# SCH_FT232H.net
KiCad netlist of a schematic drawn in Altium Designer
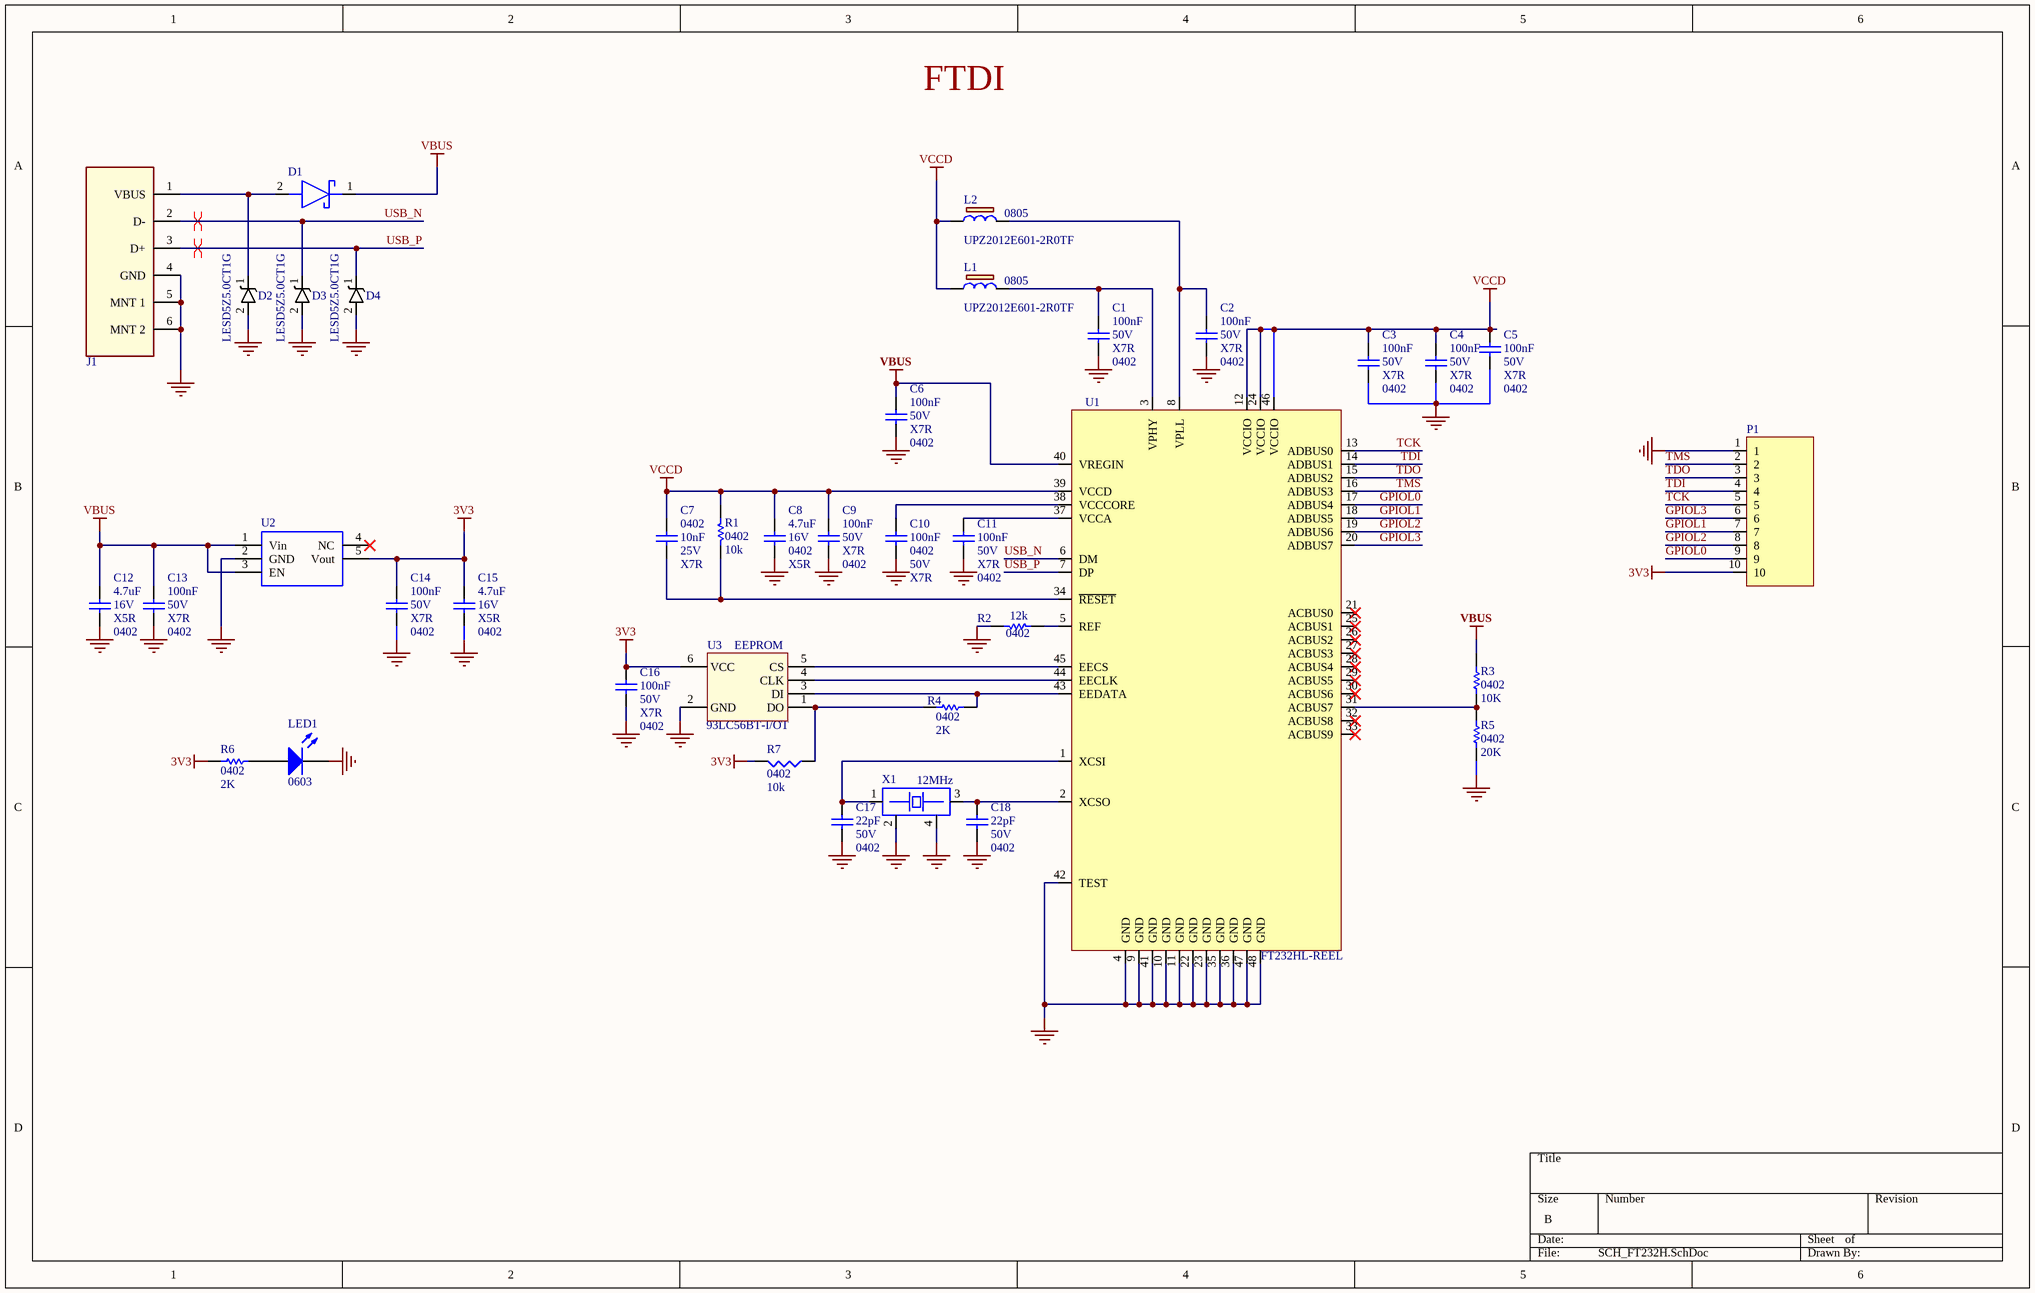
[diagram p0: SCH_FT232H.SchDoc]

(export (version "E")
  (design (tool "Eeschema 10.0.6"))
  (components
    (comp (ref "C1")
      (value "100nF")
      (footprint "CAPC0402")
      (description "CAP CER 100nF 50V X7R 0402")
      (fields
        (field (name "CASE/PACKAGE") "0402")
        (field (name "VOLTAGE") "50V")
        (field (name "DIELECTRIC") "X7R")
      )
      (libsource (lib "Pd's Sch Lib") (part "Capacitor"))
    )
    (comp (ref "C2")
      (value "100nF")
      (footprint "CAPC0402")
      (description "CAP CER 100nF 50V X7R 0402")
      (fields
        (field (name "CASE/PACKAGE") "0402")
        (field (name "VOLTAGE") "50V")
        (field (name "DIELECTRIC") "X7R")
      )
      (libsource (lib "Pd's Sch Lib") (part "Capacitor"))
    )
    (comp (ref "C3")
      (value "100nF")
      (footprint "CAPC0402")
      (description "CAP CER 100nF 50V X7R 0402")
      (fields
        (field (name "CASE/PACKAGE") "0402")
        (field (name "VOLTAGE") "50V")
        (field (name "DIELECTRIC") "X7R")
      )
      (libsource (lib "Pd's Sch Lib") (part "Capacitor"))
    )
    (comp (ref "C4")
      (value "100nF")
      (footprint "CAPC0402")
      (description "CAP CER 100nF 50V X7R 0402")
      (fields
        (field (name "CASE/PACKAGE") "0402")
        (field (name "VOLTAGE") "50V")
        (field (name "DIELECTRIC") "X7R")
      )
      (libsource (lib "Pd's Sch Lib") (part "Capacitor"))
    )
    (comp (ref "C5")
      (value "100nF")
      (footprint "CAPC0402")
      (description "CAP CER 100nF 50V X7R 0402")
      (fields
        (field (name "CASE/PACKAGE") "0402")
        (field (name "VOLTAGE") "50V")
        (field (name "DIELECTRIC") "X7R")
      )
      (libsource (lib "Pd's Sch Lib") (part "Capacitor"))
    )
    (comp (ref "C6")
      (value "100nF")
      (footprint "CAPC0402")
      (description "CAP CER 100nF 50V X7R 0402")
      (fields
        (field (name "CASE/PACKAGE") "0402")
        (field (name "VOLTAGE") "50V")
        (field (name "DIELECTRIC") "X7R")
      )
      (libsource (lib "Pd's Sch Lib") (part "Capacitor"))
    )
    (comp (ref "C7")
      (value "10nF")
      (footprint "CAPC0402")
      (description "CAP CER 10nF 25V X7R 0402")
      (fields
        (field (name "CASE/PACKAGE") "0402")
        (field (name "VOLTAGE") "25V")
        (field (name "DIELECTRIC") "X7R")
      )
      (libsource (lib "Pd's Sch Lib") (part "Capacitor"))
    )
    (comp (ref "C8")
      (value "4.7uF")
      (footprint "CAPC0402")
      (description "CAP CER 4.7uF 16V X5R 0402")
      (fields
        (field (name "CASE/PACKAGE") "0402")
        (field (name "VOLTAGE") "16V")
        (field (name "DIELECTRIC") "X5R")
      )
      (libsource (lib "Pd's Sch Lib") (part "Capacitor"))
    )
    (comp (ref "C9")
      (value "100nF")
      (footprint "CAPC0402")
      (description "CAP CER 100nF 50V X7R 0402")
      (fields
        (field (name "CASE/PACKAGE") "0402")
        (field (name "VOLTAGE") "50V")
        (field (name "DIELECTRIC") "X7R")
      )
      (libsource (lib "Pd's Sch Lib") (part "Capacitor"))
    )
    (comp (ref "C10")
      (value "100nF")
      (footprint "CAPC0402")
      (description "CAP CER 100nF 50V X7R 0402")
      (fields
        (field (name "CASE/PACKAGE") "0402")
        (field (name "VOLTAGE") "50V")
        (field (name "DIELECTRIC") "X7R")
      )
      (libsource (lib "Pd's Sch Lib") (part "Capacitor"))
    )
    (comp (ref "C11")
      (value "100nF")
      (footprint "CAPC0402")
      (description "CAP CER 100nF 50V X7R 0402")
      (fields
        (field (name "CASE/PACKAGE") "0402")
        (field (name "VOLTAGE") "50V")
        (field (name "DIELECTRIC") "X7R")
      )
      (libsource (lib "Pd's Sch Lib") (part "Capacitor"))
    )
    (comp (ref "C12")
      (value "4.7uF")
      (footprint "CAPC0402")
      (description "CAP CER 4.7uF 16V X5R 0402")
      (fields
        (field (name "CASE/PACKAGE") "0402")
        (field (name "VOLTAGE") "16V")
        (field (name "DIELECTRIC") "X5R")
      )
      (libsource (lib "Pd's Sch Lib") (part "Capacitor"))
    )
    (comp (ref "C13")
      (value "100nF")
      (footprint "CAPC0402")
      (description "CAP CER 100nF 50V X7R 0402")
      (fields
        (field (name "CASE/PACKAGE") "0402")
        (field (name "VOLTAGE") "50V")
        (field (name "DIELECTRIC") "X7R")
      )
      (libsource (lib "Pd's Sch Lib") (part "Capacitor"))
    )
    (comp (ref "C14")
      (value "100nF")
      (footprint "CAPC0402")
      (description "CAP CER 100nF 50V X7R 0402")
      (fields
        (field (name "CASE/PACKAGE") "0402")
        (field (name "VOLTAGE") "50V")
        (field (name "DIELECTRIC") "X7R")
      )
      (libsource (lib "Pd's Sch Lib") (part "Capacitor"))
    )
    (comp (ref "C15")
      (value "4.7uF")
      (footprint "CAPC0402")
      (description "CAP CER 4.7uF 16V X5R 0402")
      (fields
        (field (name "CASE/PACKAGE") "0402")
        (field (name "VOLTAGE") "16V")
        (field (name "DIELECTRIC") "X5R")
      )
      (libsource (lib "Pd's Sch Lib") (part "Capacitor"))
    )
    (comp (ref "C16")
      (value "100nF")
      (footprint "CAPC0402")
      (description "CAP CER 100nF 50V X7R 0402")
      (fields
        (field (name "CASE/PACKAGE") "0402")
        (field (name "VOLTAGE") "50V")
        (field (name "DIELECTRIC") "X7R")
      )
      (libsource (lib "Pd's Sch Lib") (part "Capacitor"))
    )
    (comp (ref "C17")
      (value "22pF")
      (footprint "CAPC0402")
      (description "CAP CER 22pF 50V 0402")
      (fields (field (name "CASE/PACKAGE") "0402") (field (name "VOLTAGE") "50V"))
      (libsource (lib "Pd's Sch Lib") (part "Capacitor"))
    )
    (comp (ref "C18")
      (value "22pF")
      (footprint "CAPC0402")
      (description "CAP CER 22pF 50V 0402")
      (fields (field (name "CASE/PACKAGE") "0402") (field (name "VOLTAGE") "50V"))
      (libsource (lib "Pd's Sch Lib") (part "Capacitor"))
    )
    (comp (ref "D1")
      (value "~")
      (footprint "BAT760-7")
      (description "DIODE SCHOTTKY 40V 1A SOD323")
      (fields (field (name "MANUFACTURER PART NUMBER") "B5819WS"))
      (libsource (lib "CUSTOM SCH") (part "B5819WS"))
    )
    (comp (ref "D2")
      (value "~")
      (footprint "SOD523")
      (description "12.3V Clamp 8.7A (8/20µs) Ipp Tvs Diode Surface Mount SOD-523")
      (fields (field (name "MANUFACTURER PART NUMBER") "LESD5Z5.0CT1G"))
      (libsource (lib "CUSTOM TNY290PG") (part "ESD9X5.0ST5G"))
    )
    (comp (ref "D3")
      (value "~")
      (footprint "SOD523")
      (description "12.3V Clamp 8.7A (8/20µs) Ipp Tvs Diode Surface Mount SOD-523")
      (fields (field (name "MANUFACTURER PART NUMBER") "LESD5Z5.0CT1G"))
      (libsource (lib "CUSTOM TNY290PG") (part "ESD9X5.0ST5G"))
    )
    (comp (ref "D4")
      (value "~")
      (footprint "SOD523")
      (description "12.3V Clamp 8.7A (8/20µs) Ipp Tvs Diode Surface Mount SOD-523")
      (fields (field (name "MANUFACTURER PART NUMBER") "LESD5Z5.0CT1G"))
      (libsource (lib "CUSTOM TNY290PG") (part "ESD9X5.0ST5G"))
    )
    (comp (ref "J1")
      (value "~")
      (footprint "Molex_48037-0001_0")
      (description "USB A-type Plug Male PCB R/A")
      (fields (field (name "MANUFACTURER PART NUMBER") "USB Type A male"))
      (libsource (lib "CUSTOM TNY290PG") (part "USB MALE"))
    )
    (comp (ref "L1")
      (value "~")
      (footprint "ferrite bead 600R 0.5A")
      (description "Ferrite Beads 600 OHM 25% 2A")
      (fields
        (field (name "MANUFACTURER PART NUMBER") "UPZ2012E601-2R0TF")
        (field (name "CASE/PACKAGE") "0805")
      )
      (libsource (lib "CUSTOM SCH") (part "Ferrite Bead"))
    )
    (comp (ref "L2")
      (value "~")
      (footprint "ferrite bead 600R 0.5A")
      (description "Ferrite Beads 600 OHM 25% 2A")
      (fields
        (field (name "MANUFACTURER PART NUMBER") "UPZ2012E601-2R0TF")
        (field (name "CASE/PACKAGE") "0805")
      )
      (libsource (lib "CUSTOM SCH") (part "Ferrite Bead"))
    )
    (comp (ref "LED1")
      (value "~")
      (footprint "led_0603")
      (description "RED LED 0603")
      (fields (field (name "CASE/PACKAGE") "0603"))
      (libsource (lib "VEGG_Schlib") (part "LED"))
    )
    (comp (ref "P1")
      (value "~")
      (footprint "10 pin smd")
      (description "Header, 10-Pin")
      (fields (field (name "MANUFACTURER PART NUMBER") "17-Jul-2002"))
      (libsource (lib "Pd's Sch Lib") (part "Header 10"))
    )
    (comp (ref "R1")
      (value "10k")
      (footprint "RESC0402")
      (description "Thick Film Resistor -  10Kohm, 1%, 0402")
      (fields (field (name "CASE/PACKAGE") "0402"))
      (libsource (lib "Miscellaneous Devices") (part "Res1"))
    )
    (comp (ref "R2")
      (value "12k")
      (footprint "RESC0402")
      (description "Thick Film Resistor -  12Kohm, 1%, 0402")
      (fields (field (name "CASE/PACKAGE") "0402"))
      (libsource (lib "Miscellaneous Devices") (part "Res1"))
    )
    (comp (ref "R3")
      (value "10K")
      (footprint "RESC0402")
      (description "Thick Film Resistor -  10Kohm, 1%, 0402")
      (fields (field (name "CASE/PACKAGE") "0402"))
      (libsource (lib "Miscellaneous Devices") (part "Res1"))
    )
    (comp (ref "R4")
      (value "2K")
      (footprint "RESC0402")
      (description "Thick Film Resistor -  2Kohm, 1%, 0402")
      (fields (field (name "CASE/PACKAGE") "0402"))
      (libsource (lib "Miscellaneous Devices") (part "Res1"))
    )
    (comp (ref "R5")
      (value "20K")
      (footprint "RESC0402")
      (description "Thick Film Resistor -  20Kohm, 1%, 0402")
      (fields (field (name "CASE/PACKAGE") "0402"))
      (libsource (lib "Miscellaneous Devices") (part "Res1"))
    )
    (comp (ref "R6")
      (value "2K")
      (footprint "RESC0402")
      (description "Thick Film Resistor -  2Kohm, 1%, 0402")
      (fields (field (name "CASE/PACKAGE") "0402"))
      (libsource (lib "Miscellaneous Devices") (part "Res1"))
    )
    (comp (ref "R7")
      (value "10k")
      (footprint "RESC0402")
      (description "Thick Film Resistor -  10Kohm, 1%, 0402")
      (fields (field (name "CASE/PACKAGE") "0402"))
      (libsource (lib "CUSTOM TNY290PG") (part "Res"))
    )
    (comp (ref "U1")
      (value "~")
      (footprint "LQFP-48_7x7x05P__  FT232HL-REEL")
      (description "USB Interface IC USB HS to UART/FIFO SPI/JTAG/I2C LQFP-48")
      (fields (field (name "MANUFACTURER PART NUMBER") "FT232HL-REEL"))
      (libsource (lib "Pd's Sch Lib") (part "FT232HL"))
    )
    (comp (ref "U2")
      (value "~")
      (footprint "SOT25")
      (description "LDO Voltage Regulators 600mA CMOS LDO 50mA 3.3V 250mV")
      (fields (field (name "MANUFACTURER PART NUMBER") "AP2112K-3.3TRG1"))
      (libsource (lib "VEGG_Schlib") (part "LDO_5V_3V"))
    )
    (comp (ref "U3")
      (value "~")
      (footprint "SOT-23-6")
      (description "MICROCHIP - 93LC56BT-I/OT. - 2K, 128 X 16, SERIAL EE, IND ROHS COMPLIANT: YES")
      (fields
        (field (name "MANUFACTURER") "Microchip")
        (field (name "MEMORY TYPE") "EEPROM")
        (field (name "MANUFACTURER PART NUMBER") "93LC56BT-I/OT")
      )
      (libsource (lib "CUSTOM TNY290PG") (part "93LC56BT-I/OT"))
    )
    (comp (ref "X1")
      (value "~")
      (footprint "Crystal_3225")
      (description "CRYSTAL 12.0000MHZ 10PF SMD")
      (fields
        (field (name "MANUFACTURER PART NUMBER") "ECS-120-10-33B-CKM-TR")
        (field (name "FREQUENCY") "12MHz")
      )
      (libsource (lib "Pd's Sch Lib") (part "CRYSTAL_1_1"))
    )
  )
  (nets
    (net (code "1") (name "/GPIOL0") (class "Default")
      (node (ref "P1") (pin "9") (pinfunction "9_9") (pintype "passive"))
      (node (ref "U1") (pin "17") (pinfunction "ADBUS4_17") (pintype "passive"))
    )
    (net (code "2") (name "/GPIOL1") (class "Default")
      (node (ref "P1") (pin "7") (pinfunction "7_7") (pintype "passive"))
      (node (ref "U1") (pin "18") (pinfunction "ADBUS5_18") (pintype "passive"))
    )
    (net (code "3") (name "/GPIOL2") (class "Default")
      (node (ref "P1") (pin "8") (pinfunction "8_8") (pintype "passive"))
      (node (ref "U1") (pin "19") (pinfunction "ADBUS6_19") (pintype "passive"))
    )
    (net (code "4") (name "/GPIOL3") (class "Default")
      (node (ref "P1") (pin "6") (pinfunction "6_6") (pintype "passive"))
      (node (ref "U1") (pin "20") (pinfunction "ADBUS7_20") (pintype "passive"))
    )
    (net (code "5") (name "/TCK") (class "Default")
      (node (ref "P1") (pin "5") (pinfunction "5_5") (pintype "passive"))
      (node (ref "U1") (pin "13") (pinfunction "ADBUS0_13") (pintype "passive"))
    )
    (net (code "6") (name "/TDI") (class "Default")
      (node (ref "P1") (pin "4") (pinfunction "4_4") (pintype "passive"))
      (node (ref "U1") (pin "14") (pinfunction "ADBUS1_14") (pintype "passive"))
    )
    (net (code "7") (name "/TDO") (class "Default")
      (node (ref "P1") (pin "3") (pinfunction "3_3") (pintype "passive"))
      (node (ref "U1") (pin "15") (pinfunction "ADBUS2_15") (pintype "passive"))
    )
    (net (code "8") (name "/TMS") (class "Default")
      (node (ref "P1") (pin "2") (pinfunction "2_2") (pintype "passive"))
      (node (ref "U1") (pin "16") (pinfunction "ADBUS3_16") (pintype "passive"))
    )
    (net (code "9") (name "/USB_N") (class "Default")
      (node (ref "D3") (pin "1") (pinfunction "K_1") (pintype "passive"))
      (node (ref "J1") (pin "2") (pinfunction "D-_2") (pintype "passive"))
      (node (ref "U1") (pin "6") (pinfunction "DM_6") (pintype "passive"))
    )
    (net (code "10") (name "/USB_P") (class "Default")
      (node (ref "D4") (pin "1") (pinfunction "K_1") (pintype "passive"))
      (node (ref "J1") (pin "3") (pinfunction "D+_3") (pintype "passive"))
      (node (ref "U1") (pin "7") (pinfunction "DP_7") (pintype "passive"))
    )
    (net (code "11") (name "3V3") (class "Default")
      (node (ref "C14") (pin "2") (pinfunction "2_2") (pintype "passive"))
      (node (ref "C15") (pin "2") (pinfunction "2_2") (pintype "passive"))
      (node (ref "C16") (pin "2") (pinfunction "2_2") (pintype "passive"))
      (node (ref "P1") (pin "10") (pinfunction "10_10") (pintype "passive"))
      (node (ref "R6") (pin "1") (pinfunction "1_1") (pintype "passive"))
      (node (ref "R7") (pin "2") (pinfunction "2_2") (pintype "passive"))
      (node (ref "U2") (pin "5") (pinfunction "Vout_5") (pintype "power_in"))
      (node (ref "U3") (pin "6") (pinfunction "VCC_6") (pintype "passive"))
    )
    (net (code "12") (name "GND") (class "Default")
      (node (ref "C1") (pin "1") (pinfunction "1_1") (pintype "passive"))
      (node (ref "C10") (pin "1") (pinfunction "1_1") (pintype "passive"))
      (node (ref "C11") (pin "1") (pinfunction "1_1") (pintype "passive"))
      (node (ref "C12") (pin "1") (pinfunction "1_1") (pintype "passive"))
      (node (ref "C13") (pin "1") (pinfunction "1_1") (pintype "passive"))
      (node (ref "C14") (pin "1") (pinfunction "1_1") (pintype "passive"))
      (node (ref "C15") (pin "1") (pinfunction "1_1") (pintype "passive"))
      (node (ref "C16") (pin "1") (pinfunction "1_1") (pintype "passive"))
      (node (ref "C17") (pin "1") (pinfunction "1_1") (pintype "passive"))
      (node (ref "C18") (pin "1") (pinfunction "1_1") (pintype "passive"))
      (node (ref "C2") (pin "1") (pinfunction "1_1") (pintype "passive"))
      (node (ref "C3") (pin "2") (pinfunction "2_2") (pintype "passive"))
      (node (ref "C4") (pin "2") (pinfunction "2_2") (pintype "passive"))
      (node (ref "C5") (pin "2") (pinfunction "2_2") (pintype "passive"))
      (node (ref "C6") (pin "1") (pinfunction "1_1") (pintype "passive"))
      (node (ref "C8") (pin "1") (pinfunction "1_1") (pintype "passive"))
      (node (ref "C9") (pin "1") (pinfunction "1_1") (pintype "passive"))
      (node (ref "D2") (pin "2") (pinfunction "A_2") (pintype "passive"))
      (node (ref "D3") (pin "2") (pinfunction "A_2") (pintype "passive"))
      (node (ref "D4") (pin "2") (pinfunction "A_2") (pintype "passive"))
      (node (ref "J1") (pin "4") (pinfunction "GND_4") (pintype "passive"))
      (node (ref "J1") (pin "5") (pinfunction "MNT_1_5") (pintype "passive"))
      (node (ref "J1") (pin "6") (pinfunction "MNT_2_6") (pintype "passive"))
      (node (ref "LED1") (pin "K") (pinfunction "K_K") (pintype "passive"))
      (node (ref "P1") (pin "1") (pinfunction "1_1") (pintype "passive"))
      (node (ref "R2") (pin "1") (pinfunction "1_1") (pintype "passive"))
      (node (ref "R5") (pin "2") (pinfunction "2_2") (pintype "passive"))
      (node (ref "U1") (pin "10") (pinfunction "GND_10") (pintype "passive"))
      (node (ref "U1") (pin "11") (pinfunction "GND_11") (pintype "passive"))
      (node (ref "U1") (pin "22") (pinfunction "GND_22") (pintype "passive"))
      (node (ref "U1") (pin "23") (pinfunction "GND_23") (pintype "passive"))
      (node (ref "U1") (pin "35") (pinfunction "GND_35") (pintype "passive"))
      (node (ref "U1") (pin "36") (pinfunction "GND_36") (pintype "passive"))
      (node (ref "U1") (pin "4") (pinfunction "GND_4") (pintype "passive"))
      (node (ref "U1") (pin "41") (pinfunction "GND_41") (pintype "passive"))
      (node (ref "U1") (pin "42") (pinfunction "TEST_42") (pintype "passive"))
      (node (ref "U1") (pin "47") (pinfunction "GND_47") (pintype "passive"))
      (node (ref "U1") (pin "48") (pinfunction "GND_48") (pintype "passive"))
      (node (ref "U1") (pin "9") (pinfunction "GND_9") (pintype "passive"))
      (node (ref "U2") (pin "2") (pinfunction "GND_2") (pintype "power_in"))
      (node (ref "U3") (pin "2") (pinfunction "GND_2") (pintype "passive"))
      (node (ref "X1") (pin "2") (pinfunction "2_2") (pintype "passive"))
      (node (ref "X1") (pin "4") (pinfunction "4_4") (pintype "passive"))
    )
    (net (code "13") (name "Net-(D1-A)") (class "Default")
      (node (ref "D1") (pin "2") (pinfunction "A_2") (pintype "passive"))
      (node (ref "D2") (pin "1") (pinfunction "K_1") (pintype "passive"))
      (node (ref "J1") (pin "1") (pinfunction "VBUS_1") (pintype "passive"))
    )
    (net (code "14") (name "Net-(LED1-PadA)") (class "Default")
      (node (ref "LED1") (pin "A") (pinfunction "A_A") (pintype "passive"))
      (node (ref "R6") (pin "2") (pinfunction "2_2") (pintype "passive"))
    )
    (net (code "15") (name "Net-(U1-ACBUS7)") (class "Default")
      (node (ref "R3") (pin "2") (pinfunction "2_2") (pintype "passive"))
      (node (ref "R5") (pin "1") (pinfunction "1_1") (pintype "passive"))
      (node (ref "U1") (pin "31") (pinfunction "ACBUS7_31") (pintype "passive"))
    )
    (net (code "16") (name "Net-(U1-EECLK)") (class "Default")
      (node (ref "U1") (pin "44") (pinfunction "EECLK_44") (pintype "passive"))
      (node (ref "U3") (pin "4") (pinfunction "CLK_4") (pintype "passive"))
    )
    (net (code "17") (name "Net-(U1-EECS)") (class "Default")
      (node (ref "U1") (pin "45") (pinfunction "EECS_45") (pintype "passive"))
      (node (ref "U3") (pin "5") (pinfunction "CS_5") (pintype "passive"))
    )
    (net (code "18") (name "Net-(U1-EEDATA)") (class "Default")
      (node (ref "R4") (pin "2") (pinfunction "2_2") (pintype "passive"))
      (node (ref "U1") (pin "43") (pinfunction "EEDATA_43") (pintype "passive"))
      (node (ref "U3") (pin "3") (pinfunction "DI_3") (pintype "passive"))
    )
    (net (code "19") (name "Net-(U1-REF)") (class "Default")
      (node (ref "R2") (pin "2") (pinfunction "2_2") (pintype "passive"))
      (node (ref "U1") (pin "5") (pinfunction "REF_5") (pintype "passive"))
    )
    (net (code "20") (name "Net-(U1-VCCA)") (class "Default")
      (node (ref "C11") (pin "2") (pinfunction "2_2") (pintype "passive"))
      (node (ref "U1") (pin "37") (pinfunction "VCCA_37") (pintype "passive"))
    )
    (net (code "21") (name "Net-(U1-VCCCORE)") (class "Default")
      (node (ref "C10") (pin "2") (pinfunction "2_2") (pintype "passive"))
      (node (ref "U1") (pin "38") (pinfunction "VCCCORE_38") (pintype "passive"))
    )
    (net (code "22") (name "Net-(U1-VPHY)") (class "Default")
      (node (ref "C1") (pin "2") (pinfunction "2_2") (pintype "passive"))
      (node (ref "L1") (pin "2") (pintype "passive"))
      (node (ref "U1") (pin "3") (pinfunction "VPHY_3") (pintype "passive"))
    )
    (net (code "23") (name "Net-(U1-VPLL)") (class "Default")
      (node (ref "C2") (pin "2") (pinfunction "2_2") (pintype "passive"))
      (node (ref "L2") (pin "2") (pintype "passive"))
      (node (ref "U1") (pin "8") (pinfunction "VPLL_8") (pintype "passive"))
    )
    (net (code "24") (name "Net-(U1-XCSI)") (class "Default")
      (node (ref "C17") (pin "2") (pinfunction "2_2") (pintype "passive"))
      (node (ref "U1") (pin "1") (pinfunction "XCSI_1") (pintype "passive"))
      (node (ref "X1") (pin "1") (pinfunction "1_1") (pintype "passive"))
    )
    (net (code "25") (name "Net-(U1-XCSO)") (class "Default")
      (node (ref "C18") (pin "2") (pinfunction "2_2") (pintype "passive"))
      (node (ref "U1") (pin "2") (pinfunction "XCSO_2") (pintype "passive"))
      (node (ref "X1") (pin "3") (pinfunction "3_3") (pintype "passive"))
    )
    (net (code "26") (name "Net-(U1-~{RESET})") (class "Default")
      (node (ref "C7") (pin "1") (pinfunction "1_1") (pintype "passive"))
      (node (ref "R1") (pin "1") (pinfunction "1_1") (pintype "passive"))
      (node (ref "U1") (pin "34") (pinfunction "~{RESET}_34") (pintype "passive"))
    )
    (net (code "27") (name "Net-(U3-DO)") (class "Default")
      (node (ref "R4") (pin "1") (pinfunction "1_1") (pintype "passive"))
      (node (ref "R7") (pin "1") (pinfunction "1_1") (pintype "passive"))
      (node (ref "U3") (pin "1") (pinfunction "DO_1") (pintype "passive"))
    )
    (net (code "28") (name "VBUS") (class "Default")
      (node (ref "C12") (pin "2") (pinfunction "2_2") (pintype "passive"))
      (node (ref "C13") (pin "2") (pinfunction "2_2") (pintype "passive"))
      (node (ref "C6") (pin "2") (pinfunction "2_2") (pintype "passive"))
      (node (ref "D1") (pin "1") (pinfunction "K_1") (pintype "passive"))
      (node (ref "R3") (pin "1") (pinfunction "1_1") (pintype "passive"))
      (node (ref "U1") (pin "40") (pinfunction "VREGIN_40") (pintype "passive"))
      (node (ref "U2") (pin "1") (pinfunction "Vin_1") (pintype "power_in"))
      (node (ref "U2") (pin "3") (pinfunction "EN_3") (pintype "passive"))
    )
    (net (code "29") (name "VCCD") (class "Default")
      (node (ref "C3") (pin "1") (pinfunction "1_1") (pintype "passive"))
      (node (ref "C4") (pin "1") (pinfunction "1_1") (pintype "passive"))
      (node (ref "C5") (pin "1") (pinfunction "1_1") (pintype "passive"))
      (node (ref "C7") (pin "2") (pinfunction "2_2") (pintype "passive"))
      (node (ref "C8") (pin "2") (pinfunction "2_2") (pintype "passive"))
      (node (ref "C9") (pin "2") (pinfunction "2_2") (pintype "passive"))
      (node (ref "L1") (pin "1") (pintype "passive"))
      (node (ref "L2") (pin "1") (pintype "passive"))
      (node (ref "R1") (pin "2") (pinfunction "2_2") (pintype "passive"))
      (node (ref "U1") (pin "12") (pinfunction "VCCIO_12") (pintype "passive"))
      (node (ref "U1") (pin "24") (pinfunction "VCCIO_24") (pintype "passive"))
      (node (ref "U1") (pin "39") (pinfunction "VCCD_39") (pintype "passive"))
      (node (ref "U1") (pin "46") (pinfunction "VCCIO_46") (pintype "passive"))
    )
    (net (code "30") (name "unconnected-(U1-ACBUS0-Pad21)") (class "Default")
      (node (ref "U1") (pin "21") (pinfunction "ACBUS0_21") (pintype "passive+no_connect"))
    )
    (net (code "31") (name "unconnected-(U1-ACBUS1-Pad25)") (class "Default")
      (node (ref "U1") (pin "25") (pinfunction "ACBUS1_25") (pintype "passive+no_connect"))
    )
    (net (code "32") (name "unconnected-(U1-ACBUS2-Pad26)") (class "Default")
      (node (ref "U1") (pin "26") (pinfunction "ACBUS2_26") (pintype "passive+no_connect"))
    )
    (net (code "33") (name "unconnected-(U1-ACBUS3-Pad27)") (class "Default")
      (node (ref "U1") (pin "27") (pinfunction "ACBUS3_27") (pintype "passive+no_connect"))
    )
    (net (code "34") (name "unconnected-(U1-ACBUS4-Pad28)") (class "Default")
      (node (ref "U1") (pin "28") (pinfunction "ACBUS4_28") (pintype "passive+no_connect"))
    )
    (net (code "35") (name "unconnected-(U1-ACBUS5-Pad29)") (class "Default")
      (node (ref "U1") (pin "29") (pinfunction "ACBUS5_29") (pintype "passive+no_connect"))
    )
    (net (code "36") (name "unconnected-(U1-ACBUS6-Pad30)") (class "Default")
      (node (ref "U1") (pin "30") (pinfunction "ACBUS6_30") (pintype "passive+no_connect"))
    )
    (net (code "37") (name "unconnected-(U1-ACBUS8-Pad32)") (class "Default")
      (node (ref "U1") (pin "32") (pinfunction "ACBUS8_32") (pintype "passive+no_connect"))
    )
    (net (code "38") (name "unconnected-(U1-ACBUS9-Pad33)") (class "Default")
      (node (ref "U1") (pin "33") (pinfunction "ACBUS9_33") (pintype "passive+no_connect"))
    )
    (net (code "39") (name "unconnected-(U2-NC-Pad4)") (class "Default")
      (node (ref "U2") (pin "4") (pinfunction "NC_4") (pintype "passive+no_connect"))
    )
  )
)
